# ottSchematic.net
KiCad netlist of a schematic drawn in EAGLE
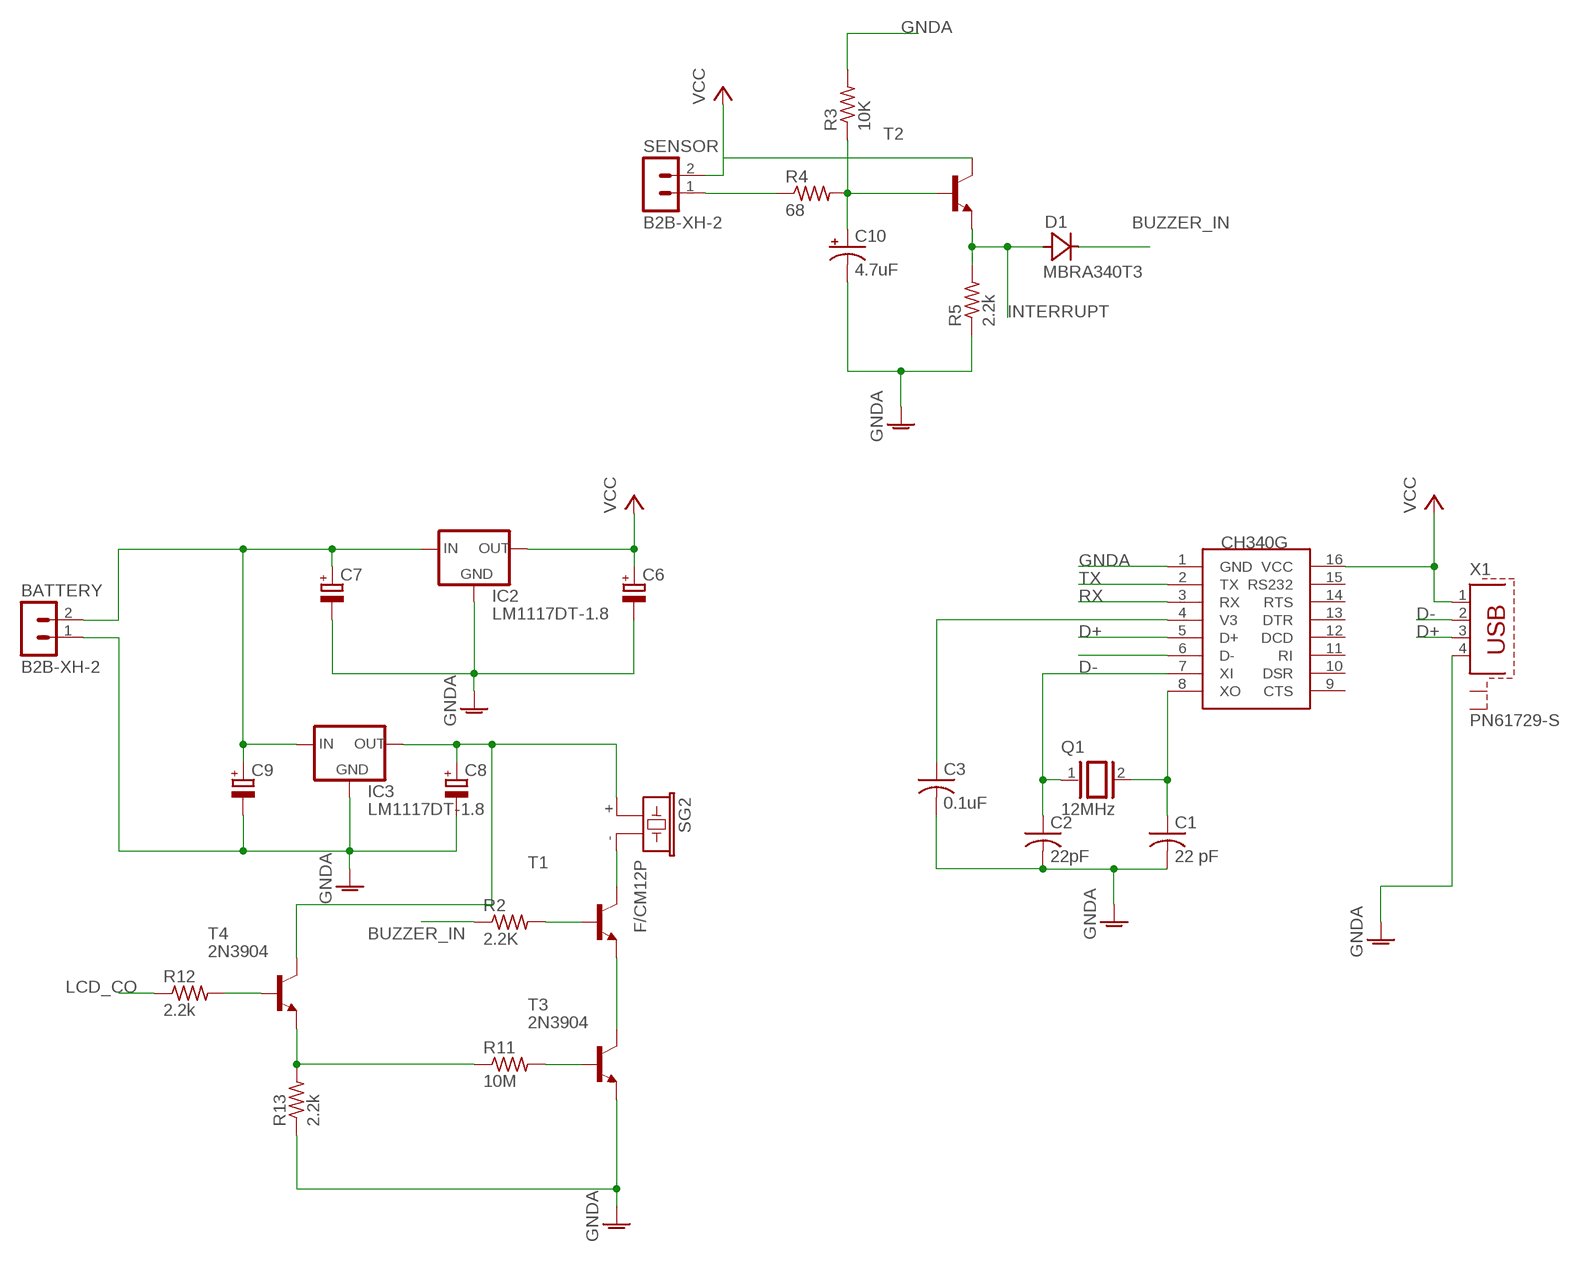
[diagram p0: schematic, sheet 1]
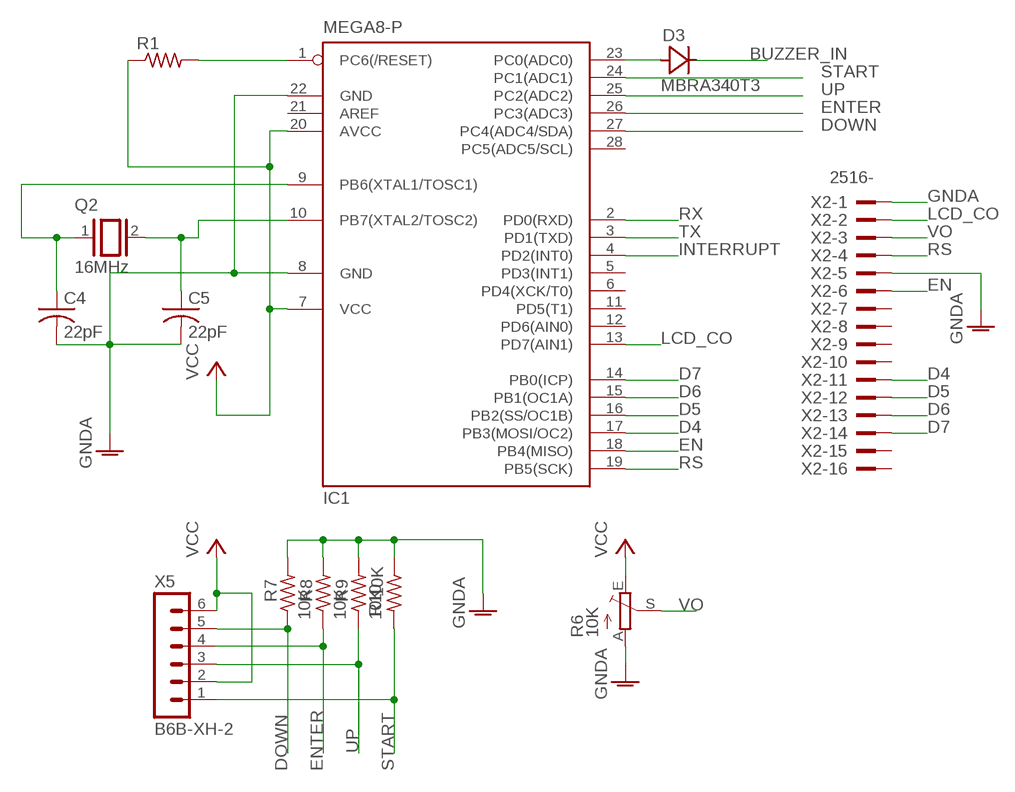
[diagram p1: schematic, sheet 2]

(export (version "E")
  (design (tool "Eeschema 10.0.6"))
  (components
    (comp (ref "C4")
      (value "22pF")
      (footprint "eagle-import:C0805")
      (libsource (lib "eagle-import") (part "C-USC0805"))
    )
    (comp (ref "C5")
      (value "22pF")
      (footprint "eagle-import:C0805")
      (libsource (lib "eagle-import") (part "C-USC0805"))
    )
    (comp (ref "D3")
      (value "MBRA340T3")
      (footprint "eagle-import:SMA")
      (libsource (lib "eagle-import") (part "MBRA340T3"))
    )
    (comp (ref "IC1")
      (value "MEGA8-P")
      (footprint "eagle-import:DIL28-3")
      (libsource (lib "eagle-import") (part "MEGA8-P"))
    )
    (comp (ref "Q2")
      (value "16MHz")
      (footprint "eagle-import:QS")
      (libsource (lib "eagle-import") (part "XTAL/S"))
    )
    (comp (ref "R1")
      (value "R-US_R0805")
      (footprint "eagle-import:R0805")
      (libsource (lib "eagle-import") (part "R-US_R0805"))
    )
    (comp (ref "R6")
      (value "10K")
      (footprint "eagle-import:B64Y")
      (libsource (lib "eagle-import") (part "TRIM_EU-B64Y"))
    )
    (comp (ref "R7")
      (value "10K")
      (footprint "eagle-import:R0805")
      (libsource (lib "eagle-import") (part "R-US_R0805"))
    )
    (comp (ref "R8")
      (value "10K")
      (footprint "eagle-import:R0805")
      (libsource (lib "eagle-import") (part "R-US_R0805"))
    )
    (comp (ref "R9")
      (value "10K")
      (footprint "eagle-import:R0805")
      (libsource (lib "eagle-import") (part "R-US_R0805"))
    )
    (comp (ref "R10")
      (value "10K")
      (footprint "eagle-import:R0805")
      (libsource (lib "eagle-import") (part "R-US_R0805"))
    )
    (comp (ref "X2")
      (value "2516-")
      (footprint "eagle-import:PAK100_2500-16")
      (libsource (lib "eagle-import") (part "2516-"))
    )
    (comp (ref "X5")
      (value "B6B-XH-2")
      (footprint "eagle-import:B6B-XH-A")
      (libsource (lib "eagle-import") (part "B6B-XH-2"))
    )
    (comp (ref "BATTERY")
      (value "B2B-XH-2")
      (footprint "eagle-import:B2B-XH-A")
      (libsource (lib "eagle-import") (part "B2B-XH-2"))
    )
    (comp (ref "C1")
      (value "22 pF")
      (footprint "eagle-import:C0603K")
      (libsource (lib "eagle-import") (part "C-USC0603K"))
    )
    (comp (ref "C2")
      (value "22pF")
      (footprint "eagle-import:C0603K")
      (libsource (lib "eagle-import") (part "C-USC0603K"))
    )
    (comp (ref "C3")
      (value "0.1uF")
      (footprint "eagle-import:C1206K")
      (libsource (lib "eagle-import") (part "C-USC1206K"))
    )
    (comp (ref "C6")
      (value "CPOL-EU175TMP-0808")
      (footprint "eagle-import:175TMP-0808")
      (libsource (lib "eagle-import") (part "CPOL-EU175TMP-0808"))
    )
    (comp (ref "C7")
      (value "CPOL-EU175TMP-0808")
      (footprint "eagle-import:175TMP-0808")
      (libsource (lib "eagle-import") (part "CPOL-EU175TMP-0808"))
    )
    (comp (ref "C8")
      (value "CPOL-EU175TMP-0808")
      (footprint "eagle-import:175TMP-0808")
      (libsource (lib "eagle-import") (part "CPOL-EU175TMP-0808"))
    )
    (comp (ref "C9")
      (value "CPOL-EU175TMP-0808")
      (footprint "eagle-import:175TMP-0808")
      (libsource (lib "eagle-import") (part "CPOL-EU175TMP-0808"))
    )
    (comp (ref "C10")
      (value "4.7uF")
      (footprint "eagle-import:E5-8,5")
      (libsource (lib "eagle-import") (part "CPOL-USE5-8.5"))
    )
    (comp (ref "D1")
      (value "MBRA340T3")
      (footprint "eagle-import:SMA")
      (libsource (lib "eagle-import") (part "MBRA340T3"))
    )
    (comp (ref "IC2")
      (value "LM1117DT-1.8")
      (footprint "eagle-import:TO252")
      (fields (field (name "MF") "Texas Instruments"))
      (libsource (lib "eagle-import") (part "LM1117?-DT1.8"))
    )
    (comp (ref "IC3")
      (value "LM1117DT-1.8")
      (footprint "eagle-import:TO252")
      (fields (field (name "MF") "Texas Instruments"))
      (libsource (lib "eagle-import") (part "LM1117?-DT1.8"))
    )
    (comp (ref "Q1")
      (value "12MHz")
      (footprint "eagle-import:QS")
      (libsource (lib "eagle-import") (part "XTAL/S"))
    )
    (comp (ref "R2")
      (value "2.2K")
      (footprint "eagle-import:R0805")
      (libsource (lib "eagle-import") (part "R-US_R0805"))
    )
    (comp (ref "R3")
      (value "10K")
      (footprint "eagle-import:R0805")
      (libsource (lib "eagle-import") (part "R-US_R0805"))
    )
    (comp (ref "R4")
      (value "68")
      (footprint "eagle-import:0309_12")
      (libsource (lib "eagle-import") (part "R-US_0309/12"))
    )
    (comp (ref "R5")
      (value "2.2k")
      (footprint "eagle-import:R0805")
      (libsource (lib "eagle-import") (part "R-US_R0805"))
    )
    (comp (ref "R11")
      (value "10M")
      (footprint "eagle-import:R0805")
      (libsource (lib "eagle-import") (part "R-US_R0805"))
    )
    (comp (ref "R12")
      (value "2.2k")
      (footprint "eagle-import:R0805")
      (libsource (lib "eagle-import") (part "R-US_R0805"))
    )
    (comp (ref "R13")
      (value "2.2k")
      (footprint "eagle-import:R0805")
      (libsource (lib "eagle-import") (part "R-US_R0805"))
    )
    (comp (ref "SENSOR")
      (value "B2B-XH-2")
      (footprint "eagle-import:B2B-XH-A")
      (libsource (lib "eagle-import") (part "B2B-XH-2"))
    )
    (comp (ref "SG2")
      (value "F/CM12P")
      (footprint "eagle-import:F_CM12P")
      (libsource (lib "eagle-import") (part "F/CM12P"))
    )
    (comp (ref "T1")
      (value "MMBT3904LT1-NPN-SOT23-BEC")
      (footprint "eagle-import:SOT23-BEC")
      (libsource (lib "eagle-import") (part "-NPN-SOT23-BECMMBT3904LT1"))
    )
    (comp (ref "T2")
      (value "MMBT3904LT1-NPN-SOT23-BEC")
      (footprint "eagle-import:SOT23-BEC")
      (libsource (lib "eagle-import") (part "-NPN-SOT23-BECMMBT3904LT1"))
    )
    (comp (ref "T3")
      (value "2N3904")
      (footprint "eagle-import:TO92")
      (libsource (lib "eagle-import") (part "2N3904"))
    )
    (comp (ref "T4")
      (value "2N3904")
      (footprint "eagle-import:TO92")
      (libsource (lib "eagle-import") (part "2N3904"))
    )
    (comp (ref "U$1")
      (value "CH340G")
      (footprint "eagle-import:SOIC16")
      (libsource (lib "eagle-import") (part "CH340G"))
    )
    (comp (ref "X1")
      (value "PN61729-S")
      (footprint "eagle-import:PN61729-S")
      (libsource (lib "eagle-import") (part "PN61729-S"))
    )
  )
  (nets
    (net (code "1") (name "BUZZER_IN") (class "Default")
      (node (ref "D1") (pin "C") (pinfunction "C_C") (pintype "passive"))
      (node (ref "D3") (pin "C") (pinfunction "C_C") (pintype "passive"))
      (node (ref "R2") (pin "1") (pinfunction "1_1") (pintype "passive"))
    )
    (net (code "2") (name "D+") (class "Default")
      (node (ref "U$1") (pin "5") (pinfunction "D+_5") (pintype "bidirectional"))
      (node (ref "X1") (pin "3") (pinfunction "3_3") (pintype "passive"))
    )
    (net (code "3") (name "D-") (class "Default")
      (node (ref "U$1") (pin "6") (pinfunction "D-_6") (pintype "bidirectional"))
      (node (ref "X1") (pin "2") (pinfunction "2_2") (pintype "passive"))
    )
    (net (code "4") (name "D4") (class "Default")
      (node (ref "IC1") (pin "17") (pinfunction "PB3(MOSI/OC2)_17") (pintype "bidirectional"))
      (node (ref "X2") (pin "11") (pinfunction "KL_11") (pintype "passive"))
    )
    (net (code "5") (name "D5") (class "Default")
      (node (ref "IC1") (pin "16") (pinfunction "PB2(SS/OC1B)_16") (pintype "bidirectional"))
      (node (ref "X2") (pin "12") (pinfunction "KL_12") (pintype "passive"))
    )
    (net (code "6") (name "D6") (class "Default")
      (node (ref "IC1") (pin "15") (pinfunction "PB1(OC1A)_15") (pintype "bidirectional"))
      (node (ref "X2") (pin "13") (pinfunction "KL_13") (pintype "passive"))
    )
    (net (code "7") (name "D7") (class "Default")
      (node (ref "IC1") (pin "14") (pinfunction "PB0(ICP)_14") (pintype "bidirectional"))
      (node (ref "X2") (pin "14") (pinfunction "KL_14") (pintype "passive"))
    )
    (net (code "8") (name "DOWN") (class "Default")
      (node (ref "IC1") (pin "27") (pinfunction "PC4(ADC4/SDA)_27") (pintype "bidirectional"))
      (node (ref "R7") (pin "1") (pinfunction "1_1") (pintype "passive"))
      (node (ref "X5") (pin "5") (pinfunction "5_5") (pintype "passive"))
    )
    (net (code "9") (name "EN") (class "Default")
      (node (ref "IC1") (pin "18") (pinfunction "PB4(MISO)_18") (pintype "bidirectional"))
      (node (ref "X2") (pin "6") (pinfunction "KL_6") (pintype "passive"))
    )
    (net (code "10") (name "ENTER") (class "Default")
      (node (ref "IC1") (pin "26") (pinfunction "PC3(ADC3)_26") (pintype "bidirectional"))
      (node (ref "R8") (pin "1") (pinfunction "1_1") (pintype "passive"))
      (node (ref "X5") (pin "4") (pinfunction "4_4") (pintype "passive"))
    )
    (net (code "11") (name "GNDA") (class "Default")
      (node (ref "BATTERY") (pin "1") (pinfunction "1_1") (pintype "passive"))
      (node (ref "C1") (pin "2") (pinfunction "2_2") (pintype "passive"))
      (node (ref "C10") (pin "-") (pinfunction "-_-") (pintype "passive"))
      (node (ref "C2") (pin "2") (pinfunction "2_2") (pintype "passive"))
      (node (ref "C3") (pin "2") (pinfunction "2_2") (pintype "passive"))
      (node (ref "C4") (pin "2") (pinfunction "2_2") (pintype "passive"))
      (node (ref "C5") (pin "2") (pinfunction "2_2") (pintype "passive"))
      (node (ref "C6") (pin "-") (pinfunction "-_-") (pintype "passive"))
      (node (ref "C7") (pin "-") (pinfunction "-_-") (pintype "passive"))
      (node (ref "C8") (pin "-") (pinfunction "-_-") (pintype "passive"))
      (node (ref "C9") (pin "-") (pinfunction "-_-") (pintype "passive"))
      (node (ref "IC1") (pin "22") (pinfunction "GND_22") (pintype "power_in"))
      (node (ref "IC1") (pin "8") (pinfunction "GND_8") (pintype "power_in"))
      (node (ref "IC2") (pin "1") (pinfunction "GND_1") (pintype "input"))
      (node (ref "IC3") (pin "1") (pinfunction "GND_1") (pintype "input"))
      (node (ref "R10") (pin "1") (pinfunction "1_1") (pintype "passive"))
      (node (ref "R13") (pin "1") (pinfunction "1_1") (pintype "passive"))
      (node (ref "R3") (pin "2") (pinfunction "2_2") (pintype "passive"))
      (node (ref "R5") (pin "1") (pinfunction "1_1") (pintype "passive"))
      (node (ref "R6") (pin "A") (pinfunction "A_A") (pintype "passive"))
      (node (ref "R7") (pin "2") (pinfunction "2_2") (pintype "passive"))
      (node (ref "R8") (pin "2") (pinfunction "2_2") (pintype "passive"))
      (node (ref "R9") (pin "2") (pinfunction "2_2") (pintype "passive"))
      (node (ref "T3") (pin "3") (pinfunction "E_3") (pintype "passive"))
      (node (ref "U$1") (pin "1") (pinfunction "GND_1") (pintype "bidirectional"))
      (node (ref "X1") (pin "4") (pinfunction "4_4") (pintype "passive"))
      (node (ref "X2") (pin "1") (pinfunction "KL_1") (pintype "passive"))
      (node (ref "X2") (pin "5") (pinfunction "KL_5") (pintype "passive"))
    )
    (net (code "12") (name "INTERRUPT") (class "Default")
      (node (ref "D1") (pin "A") (pinfunction "A_A") (pintype "passive"))
      (node (ref "IC1") (pin "4") (pinfunction "PD2(INT0)_4") (pintype "bidirectional"))
      (node (ref "R5") (pin "2") (pinfunction "2_2") (pintype "passive"))
      (node (ref "T2") (pin "E") (pinfunction "E_E") (pintype "passive"))
    )
    (net (code "13") (name "LCD_CO") (class "Default")
      (node (ref "IC1") (pin "13") (pinfunction "PD7(AIN1)_13") (pintype "bidirectional"))
      (node (ref "R12") (pin "1") (pinfunction "1_1") (pintype "passive"))
      (node (ref "X2") (pin "2") (pinfunction "KL_2") (pintype "passive"))
    )
    (net (code "14") (name "Net-(C10-Pad+)") (class "Default")
      (node (ref "C10") (pin "+") (pinfunction "+_+") (pintype "passive"))
      (node (ref "R3") (pin "1") (pinfunction "1_1") (pintype "passive"))
      (node (ref "R4") (pin "2") (pinfunction "2_2") (pintype "passive"))
      (node (ref "T2") (pin "B") (pinfunction "B_B") (pintype "passive"))
    )
    (net (code "15") (name "Net-(IC1-PB6(XTAL1{slash}TOSC1))") (class "Default")
      (node (ref "C4") (pin "1") (pinfunction "1_1") (pintype "passive"))
      (node (ref "IC1") (pin "9") (pinfunction "PB6(XTAL1/TOSC1)_9") (pintype "bidirectional"))
      (node (ref "Q2") (pin "1") (pinfunction "1_1") (pintype "passive"))
    )
    (net (code "16") (name "Net-(IC1-PB7(XTAL2{slash}TOSC2))") (class "Default")
      (node (ref "C5") (pin "1") (pinfunction "1_1") (pintype "passive"))
      (node (ref "IC1") (pin "10") (pinfunction "PB7(XTAL2/TOSC2)_10") (pintype "bidirectional"))
      (node (ref "Q2") (pin "2") (pinfunction "2_2") (pintype "passive"))
    )
    (net (code "17") (name "Net-(IC1-PC0(ADC0))") (class "Default")
      (node (ref "D3") (pin "A") (pinfunction "A_A") (pintype "passive"))
      (node (ref "IC1") (pin "23") (pinfunction "PC0(ADC0)_23") (pintype "bidirectional"))
    )
    (net (code "18") (name "Net-(IC1-PC6({slash}RESET))") (class "Default")
      (node (ref "IC1") (pin "1") (pinfunction "PC6(/RESET)_1") (pintype "bidirectional"))
      (node (ref "R1") (pin "2") (pinfunction "2_2") (pintype "passive"))
    )
    (net (code "19") (name "Net-(IC2-IN)") (class "Default")
      (node (ref "BATTERY") (pin "2") (pinfunction "2_2") (pintype "passive"))
      (node (ref "C7") (pin "+") (pinfunction "+_+") (pintype "passive"))
      (node (ref "C9") (pin "+") (pinfunction "+_+") (pintype "passive"))
      (node (ref "IC2") (pin "2") (pinfunction "IN_2") (pintype "input"))
      (node (ref "IC3") (pin "2") (pinfunction "IN_2") (pintype "input"))
    )
    (net (code "20") (name "Net-(IC3-OUT)") (class "Default")
      (node (ref "C8") (pin "+") (pinfunction "+_+") (pintype "passive"))
      (node (ref "IC3") (pin "3") (pinfunction "OUT_3") (pintype "passive"))
      (node (ref "SG2") (pin "+") (pinfunction "1_+") (pintype "passive"))
      (node (ref "T4") (pin "1") (pinfunction "C_1") (pintype "passive"))
    )
    (net (code "21") (name "Net-(R2-Pad2)") (class "Default")
      (node (ref "R2") (pin "2") (pinfunction "2_2") (pintype "passive"))
      (node (ref "T1") (pin "B") (pinfunction "B_B") (pintype "passive"))
    )
    (net (code "22") (name "Net-(R4-Pad1)") (class "Default")
      (node (ref "R4") (pin "1") (pinfunction "1_1") (pintype "passive"))
      (node (ref "SENSOR") (pin "1") (pinfunction "1_1") (pintype "passive"))
    )
    (net (code "23") (name "Net-(SG2-2)") (class "Default")
      (node (ref "SG2") (pin "-") (pinfunction "2_-") (pintype "passive"))
      (node (ref "T1") (pin "C") (pinfunction "C_C") (pintype "passive"))
    )
    (net (code "24") (name "Net-(T3-B)") (class "Default")
      (node (ref "R11") (pin "2") (pinfunction "2_2") (pintype "passive"))
      (node (ref "T3") (pin "2") (pinfunction "B_2") (pintype "passive"))
    )
    (net (code "25") (name "Net-(T3-C)") (class "Default")
      (node (ref "T1") (pin "E") (pinfunction "E_E") (pintype "passive"))
      (node (ref "T3") (pin "1") (pinfunction "C_1") (pintype "passive"))
    )
    (net (code "26") (name "Net-(T4-B)") (class "Default")
      (node (ref "R12") (pin "2") (pinfunction "2_2") (pintype "passive"))
      (node (ref "T4") (pin "2") (pinfunction "B_2") (pintype "passive"))
    )
    (net (code "27") (name "Net-(T4-E)") (class "Default")
      (node (ref "R11") (pin "1") (pinfunction "1_1") (pintype "passive"))
      (node (ref "R13") (pin "2") (pinfunction "2_2") (pintype "passive"))
      (node (ref "T4") (pin "3") (pinfunction "E_3") (pintype "passive"))
    )
    (net (code "28") (name "Net-(U$1-V3)") (class "Default")
      (node (ref "C3") (pin "1") (pinfunction "1_1") (pintype "passive"))
      (node (ref "U$1") (pin "4") (pinfunction "V3_4") (pintype "bidirectional"))
    )
    (net (code "29") (name "Net-(U$1-XI)") (class "Default")
      (node (ref "C2") (pin "1") (pinfunction "1_1") (pintype "passive"))
      (node (ref "Q1") (pin "1") (pinfunction "1_1") (pintype "passive"))
      (node (ref "U$1") (pin "7") (pinfunction "XI_7") (pintype "bidirectional"))
    )
    (net (code "30") (name "Net-(U$1-XO)") (class "Default")
      (node (ref "C1") (pin "1") (pinfunction "1_1") (pintype "passive"))
      (node (ref "Q1") (pin "2") (pinfunction "2_2") (pintype "passive"))
      (node (ref "U$1") (pin "8") (pinfunction "XO_8") (pintype "bidirectional"))
    )
    (net (code "31") (name "RS") (class "Default")
      (node (ref "IC1") (pin "19") (pinfunction "PB5(SCK)_19") (pintype "bidirectional"))
      (node (ref "X2") (pin "4") (pinfunction "KL_4") (pintype "passive"))
    )
    (net (code "32") (name "RX") (class "Default")
      (node (ref "IC1") (pin "2") (pinfunction "PD0(RXD)_2") (pintype "bidirectional"))
      (node (ref "U$1") (pin "3") (pinfunction "RX_3") (pintype "bidirectional"))
    )
    (net (code "33") (name "START") (class "Default")
      (node (ref "IC1") (pin "24") (pinfunction "PC1(ADC1)_24") (pintype "bidirectional"))
      (node (ref "R10") (pin "2") (pinfunction "2_2") (pintype "passive"))
      (node (ref "X5") (pin "1") (pinfunction "1_1") (pintype "passive"))
    )
    (net (code "34") (name "TX") (class "Default")
      (node (ref "IC1") (pin "3") (pinfunction "PD1(TXD)_3") (pintype "bidirectional"))
      (node (ref "U$1") (pin "2") (pinfunction "TX_2") (pintype "bidirectional"))
    )
    (net (code "35") (name "UP") (class "Default")
      (node (ref "IC1") (pin "25") (pinfunction "PC2(ADC2)_25") (pintype "bidirectional"))
      (node (ref "R9") (pin "1") (pinfunction "1_1") (pintype "passive"))
      (node (ref "X5") (pin "3") (pinfunction "3_3") (pintype "passive"))
    )
    (net (code "36") (name "VCC") (class "Default")
      (node (ref "C6") (pin "+") (pinfunction "+_+") (pintype "passive"))
      (node (ref "IC1") (pin "20") (pinfunction "AVCC_20") (pintype "power_in"))
      (node (ref "IC1") (pin "7") (pinfunction "VCC_7") (pintype "power_in"))
      (node (ref "IC2") (pin "3") (pinfunction "OUT_3") (pintype "passive"))
      (node (ref "R1") (pin "1") (pinfunction "1_1") (pintype "passive"))
      (node (ref "R6") (pin "E") (pinfunction "E_E") (pintype "passive"))
      (node (ref "SENSOR") (pin "2") (pinfunction "2_2") (pintype "passive"))
      (node (ref "T2") (pin "C") (pinfunction "C_C") (pintype "passive"))
      (node (ref "U$1") (pin "16") (pinfunction "VCC_16") (pintype "bidirectional"))
      (node (ref "X1") (pin "1") (pinfunction "1_1") (pintype "passive"))
      (node (ref "X5") (pin "2") (pinfunction "2_2") (pintype "passive"))
      (node (ref "X5") (pin "6") (pinfunction "6_6") (pintype "passive"))
    )
    (net (code "37") (name "VO") (class "Default")
      (node (ref "R6") (pin "S") (pinfunction "S_S") (pintype "passive"))
      (node (ref "X2") (pin "3") (pinfunction "KL_3") (pintype "passive"))
    )
    (net (code "38") (name "unconnected-(IC1-AREF-Pad21)") (class "Default")
      (node (ref "IC1") (pin "21") (pinfunction "AREF_21") (pintype "passive"))
    )
    (net (code "39") (name "unconnected-(IC1-PC5(ADC5{slash}SCL)-Pad28)") (class "Default")
      (node (ref "IC1") (pin "28") (pinfunction "PC5(ADC5/SCL)_28") (pintype "bidirectional"))
    )
    (net (code "40") (name "unconnected-(IC1-PD3(INT1)-Pad5)") (class "Default")
      (node (ref "IC1") (pin "5") (pinfunction "PD3(INT1)_5") (pintype "bidirectional"))
    )
    (net (code "41") (name "unconnected-(IC1-PD4(XCK{slash}T0)-Pad6)") (class "Default")
      (node (ref "IC1") (pin "6") (pinfunction "PD4(XCK/T0)_6") (pintype "bidirectional"))
    )
    (net (code "42") (name "unconnected-(IC1-PD5(T1)-Pad11)") (class "Default")
      (node (ref "IC1") (pin "11") (pinfunction "PD5(T1)_11") (pintype "bidirectional"))
    )
    (net (code "43") (name "unconnected-(IC1-PD6(AIN0)-Pad12)") (class "Default")
      (node (ref "IC1") (pin "12") (pinfunction "PD6(AIN0)_12") (pintype "bidirectional"))
    )
    (net (code "44") (name "unconnected-(U$1-CTS-Pad9)") (class "Default")
      (node (ref "U$1") (pin "9") (pinfunction "CTS_9") (pintype "bidirectional"))
    )
    (net (code "45") (name "unconnected-(U$1-DCD-Pad12)") (class "Default")
      (node (ref "U$1") (pin "12") (pinfunction "DCD_12") (pintype "bidirectional"))
    )
    (net (code "46") (name "unconnected-(U$1-DSR-Pad10)") (class "Default")
      (node (ref "U$1") (pin "10") (pinfunction "DSR_10") (pintype "bidirectional"))
    )
    (net (code "47") (name "unconnected-(U$1-DTR-Pad13)") (class "Default")
      (node (ref "U$1") (pin "13") (pinfunction "DTR_13") (pintype "bidirectional"))
    )
    (net (code "48") (name "unconnected-(U$1-RI-Pad11)") (class "Default")
      (node (ref "U$1") (pin "11") (pinfunction "RI_11") (pintype "bidirectional"))
    )
    (net (code "49") (name "unconnected-(U$1-RS232-Pad15)") (class "Default")
      (node (ref "U$1") (pin "15") (pinfunction "RS232_15") (pintype "bidirectional"))
    )
    (net (code "50") (name "unconnected-(U$1-RTS-Pad14)") (class "Default")
      (node (ref "U$1") (pin "14") (pinfunction "RTS_14") (pintype "bidirectional"))
    )
    (net (code "51") (name "unconnected-(X1-PadS1)") (class "Default")
      (node (ref "X1") (pin "S1") (pinfunction "S1_S1") (pintype "passive"))
    )
    (net (code "52") (name "unconnected-(X1-PadS2)") (class "Default")
      (node (ref "X1") (pin "S2") (pinfunction "S2_S2") (pintype "passive"))
    )
    (net (code "53") (name "unconnected-(X2B-KL-Pad10)") (class "Default")
      (node (ref "X2") (pin "10") (pinfunction "KL_10") (pintype "passive"))
    )
    (net (code "54") (name "unconnected-(X2G-KL-Pad15)") (class "Default")
      (node (ref "X2") (pin "15") (pinfunction "KL_15") (pintype "passive"))
    )
    (net (code "55") (name "unconnected-(X2H-KL-Pad16)") (class "Default")
      (node (ref "X2") (pin "16") (pinfunction "KL_16") (pintype "passive"))
    )
    (net (code "56") (name "unconnected-(X2N-KL-Pad7)") (class "Default")
      (node (ref "X2") (pin "7") (pinfunction "KL_7") (pintype "passive"))
    )
    (net (code "57") (name "unconnected-(X2O-KL-Pad8)") (class "Default")
      (node (ref "X2") (pin "8") (pinfunction "KL_8") (pintype "passive"))
    )
    (net (code "58") (name "unconnected-(X2P-KL-Pad9)") (class "Default")
      (node (ref "X2") (pin "9") (pinfunction "KL_9") (pintype "passive"))
    )
  )
)
